# Controller.net
KiCad netlist of a schematic drawn in EAGLE
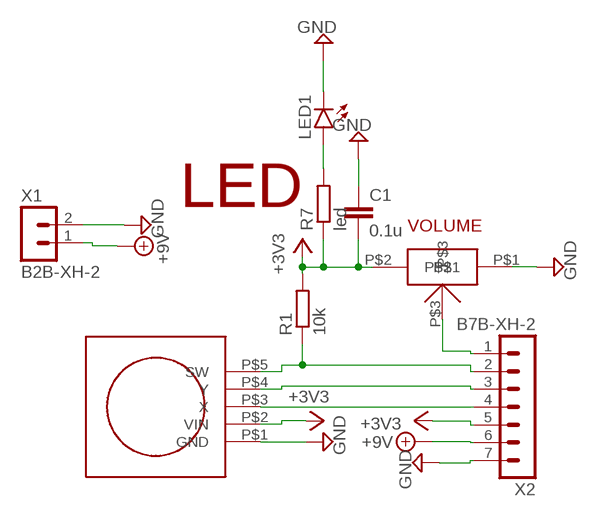
[diagram p0: schematic, sheet 1]

(export (version "E")
  (design (tool "Eeschema 10.0.6"))
  (components
    (comp (ref "C1")
      (value "0.1u")
      (footprint "eagle-import:C050-024X044")
      (libsource (lib "eagle-import") (part "C-EU050-024X044"))
    )
    (comp (ref "JOY1")
      (value "JOY")
      (footprint "eagle-import:JOY")
      (libsource (lib "eagle-import") (part "JOY"))
    )
    (comp (ref "LED1")
      (value "LED3MM")
      (footprint "eagle-import:LED3MM")
      (libsource (lib "eagle-import") (part "LED3MM"))
    )
    (comp (ref "POT1")
      (value "POTENTIOMETER")
      (footprint "eagle-import:POTENTIOMETER")
      (libsource (lib "eagle-import") (part "POTENTIOMETER"))
    )
    (comp (ref "R1")
      (value "10k")
      (footprint "eagle-import:0207_7")
      (libsource (lib "eagle-import") (part "R-EU_0207/7"))
    )
    (comp (ref "R7")
      (value "led")
      (footprint "eagle-import:0207_7")
      (libsource (lib "eagle-import") (part "R-EU_0207/7"))
    )
    (comp (ref "X1")
      (value "B2B-XH-2")
      (footprint "eagle-import:B2B-XH-A")
      (libsource (lib "eagle-import") (part "B2B-XH-2"))
    )
    (comp (ref "X2")
      (value "B7B-XH-2")
      (footprint "eagle-import:B7B-XH-A")
      (libsource (lib "eagle-import") (part "B7B-XH-2"))
    )
  )
  (nets
    (net (code "1") (name "+3V3") (class "Default")
      (node (ref "C1") (pin "2") (pinfunction "2_2") (pintype "passive"))
      (node (ref "JOY1") (pin "P$2") (pinfunction "VIN_P$2") (pintype "bidirectional"))
      (node (ref "POT1") (pin "P$2") (pinfunction "P$2_P$2") (pintype "bidirectional"))
      (node (ref "R1") (pin "2") (pinfunction "2_2") (pintype "passive"))
      (node (ref "R7") (pin "1") (pinfunction "1_1") (pintype "passive"))
      (node (ref "X2") (pin "5") (pinfunction "5_5") (pintype "passive"))
    )
    (net (code "2") (name "+9V") (class "Default")
      (node (ref "X1") (pin "1") (pinfunction "1_1") (pintype "passive"))
      (node (ref "X2") (pin "6") (pinfunction "6_6") (pintype "passive"))
    )
    (net (code "3") (name "GND") (class "Default")
      (node (ref "C1") (pin "1") (pinfunction "1_1") (pintype "passive"))
      (node (ref "JOY1") (pin "P$1") (pinfunction "GND_P$1") (pintype "bidirectional"))
      (node (ref "LED1") (pin "K") (pinfunction "C_K") (pintype "passive"))
      (node (ref "POT1") (pin "P$1") (pinfunction "P$1_P$1") (pintype "bidirectional"))
      (node (ref "X1") (pin "2") (pinfunction "2_2") (pintype "passive"))
      (node (ref "X2") (pin "7") (pinfunction "7_7") (pintype "passive"))
    )
    (net (code "4") (name "Net-(JOY1-SW)") (class "Default")
      (node (ref "JOY1") (pin "P$5") (pinfunction "SW_P$5") (pintype "bidirectional"))
      (node (ref "R1") (pin "1") (pinfunction "1_1") (pintype "passive"))
      (node (ref "X2") (pin "2") (pinfunction "2_2") (pintype "passive"))
    )
    (net (code "5") (name "Net-(JOY1-X)") (class "Default")
      (node (ref "JOY1") (pin "P$3") (pinfunction "X_P$3") (pintype "bidirectional"))
      (node (ref "X2") (pin "4") (pinfunction "4_4") (pintype "passive"))
    )
    (net (code "6") (name "Net-(JOY1-Y)") (class "Default")
      (node (ref "JOY1") (pin "P$4") (pinfunction "Y_P$4") (pintype "bidirectional"))
      (node (ref "X2") (pin "3") (pinfunction "3_3") (pintype "passive"))
    )
    (net (code "7") (name "Net-(LED1-PadA)") (class "Default")
      (node (ref "LED1") (pin "A") (pinfunction "A_A") (pintype "passive"))
      (node (ref "R7") (pin "2") (pinfunction "2_2") (pintype "passive"))
    )
    (net (code "8") (name "Net-(POT1-PadP$3)") (class "Default")
      (node (ref "POT1") (pin "P$3") (pinfunction "P$3_P$3") (pintype "bidirectional"))
      (node (ref "X2") (pin "1") (pinfunction "1_1") (pintype "passive"))
    )
  )
)
